# USB_OTG.net
KiCad netlist of a schematic drawn in Altium Designer
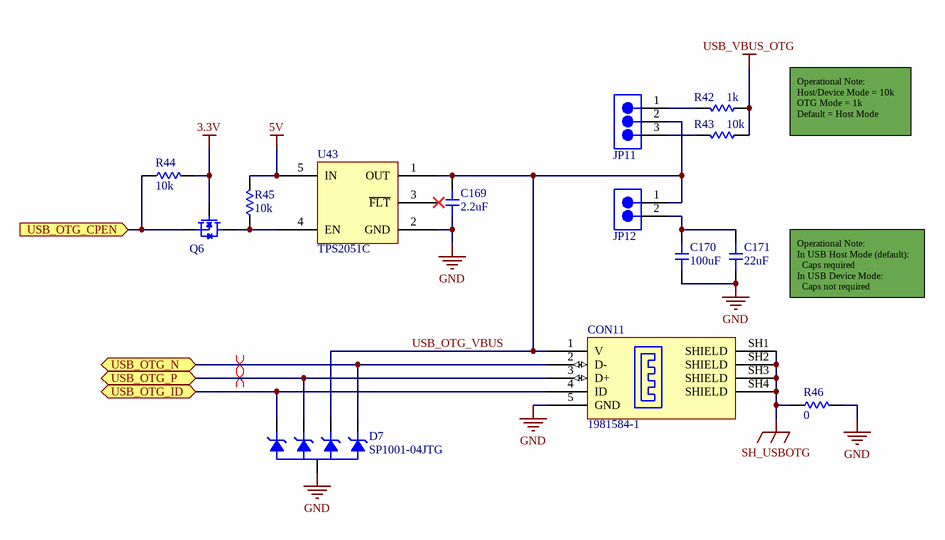
[diagram p0: USB_OTG.SchDoc]

(export (version "E")
  (design (tool "Eeschema 10.0.6"))
  (components
    (comp (ref "C169")
      (value "2.2uF")
      (footprint "0603-CAP")
      (description "Capacitor")
      (fields
        (field (name "MANUFACTURER") "Murata")
        (field (name "MANUFACTURER PART NUMBER") "GRM188R6YA225MA12D")
      )
      (libsource (lib "AMDC") (part "Capacitor"))
    )
    (comp (ref "C170")
      (value "100uF")
      (footprint "1812-CAP")
      (description "Capacitor")
      (fields
        (field (name "MANUFACTURER") "TDK")
        (field (name "MANUFACTURER PART NUMBER") "C4532X5R1A107M280KC")
      )
      (libsource (lib "AMDC") (part "Capacitor"))
    )
    (comp (ref "C171")
      (value "22uF")
      (footprint "0603-CAP")
      (description "Capacitor")
      (fields
        (field (name "MANUFACTURER") "Samsung")
        (field (name "MANUFACTURER PART NUMBER") "CL10A226MPCNUBE")
      )
      (libsource (lib "AMDC") (part "Capacitor"))
    )
    (comp (ref "CON11")
      (value "1981584-1")
      (footprint "1981584-1")
      (description "CONN RCPT MICRO USB TYPE AB")
      (fields (field (name "MANUFACTURER") "TE Connectivity"))
      (libsource (lib "AMDC") (part "1981584-1"))
    )
    (comp (ref "D7")
      (value "SP1001-04JTG")
      (footprint "SC70-5")
      (description "TVS DIODE 5.5V 13V SC70-5")
      (fields (field (name "MANUFACTURER") "Littelfuse"))
      (libsource (lib "AMDC") (part "SP1001-04JTG"))
    )
    (comp (ref "JP11")
      (value "Jumper3")
      (footprint "PIN_HEADER_1X3")
      (fields
        (field (name "MANUFACTURER") "Wurth Electronics")
        (field (name "MANUFACTURER PART NUMBER") "61300311121")
      )
      (libsource (lib "AMDC") (part "Jumper3"))
    )
    (comp (ref "JP12")
      (value "Jumper2")
      (footprint "PIN_HEADER_1x2")
      (fields
        (field (name "MANUFACTURER") "Wurth Electronics")
        (field (name "MANUFACTURER PART NUMBER") "61300211121")
      )
      (libsource (lib "AMDC") (part "Jumper2"))
    )
    (comp (ref "Q6")
      (value "MOSFET")
      (footprint "SOT95P250-3N")
      (fields (field (name "MANUFACTURER") "Diodes") (field (name "MANUFACTURER PART NUMBER") "DMN65D8L-7"))
      (libsource (lib "AMDC") (part "MOSFET"))
    )
    (comp (ref "R42")
      (value "1k")
      (footprint "0603-RES")
      (description "Resistor")
      (fields
        (field (name "MANUFACTURER") "Panasonic")
        (field (name "MANUFACTURER PART NUMBER") "ERJ-3EKF1001V")
      )
      (libsource (lib "AMDC") (part "Resistor"))
    )
    (comp (ref "R43")
      (value "10k")
      (footprint "0603-RES")
      (description "Resistor")
      (fields
        (field (name "MANUFACTURER") "Panasonic")
        (field (name "MANUFACTURER PART NUMBER") "ERJ-3EKF1002V")
      )
      (libsource (lib "AMDC") (part "Resistor"))
    )
    (comp (ref "R44")
      (value "10k")
      (footprint "0603-RES")
      (description "Resistor")
      (fields
        (field (name "MANUFACTURER") "Panasonic")
        (field (name "MANUFACTURER PART NUMBER") "ERJ-3EKF1002V")
      )
      (libsource (lib "AMDC") (part "Resistor"))
    )
    (comp (ref "R45")
      (value "10k")
      (footprint "0603-RES")
      (description "Resistor")
      (fields
        (field (name "MANUFACTURER") "Panasonic")
        (field (name "MANUFACTURER PART NUMBER") "ERJ-3EKF1002V")
      )
      (libsource (lib "AMDC") (part "Resistor"))
    )
    (comp (ref "R46")
      (value "0")
      (footprint "0603-RES")
      (description "Resistor")
      (fields
        (field (name "MANUFACTURER") "Panasonic")
        (field (name "MANUFACTURER PART NUMBER") "ERJ-3GEY0R00V")
      )
      (libsource (lib "AMDC") (part "Resistor"))
    )
    (comp (ref "U43")
      (value "TPS2051C")
      (footprint "SOT23-5")
      (description "IC USB PWR SW 1CH 0.5A SOT23-5")
      (fields
        (field (name "MANUFACTURER") "Texas Instruments")
        (field (name "MANUFACTURER PART NUMBER") "TPS2051CDBVT")
      )
      (libsource (lib "AMDC") (part "TPS2051C"))
    )
  )
  (nets
    (net (code "1") (name "/USB_OTG_CPEN") (class "Default")
      (node (ref "Q6") (pin "2") (pinfunction "S_2") (pintype "passive"))
      (node (ref "R44") (pin "1") (pinfunction "1_1") (pintype "passive"))
    )
    (net (code "2") (name "/USB_OTG_ID") (class "Default")
      (node (ref "CON11") (pin "4") (pinfunction "ID_4") (pintype "passive"))
      (node (ref "D7") (pin "1") (pinfunction "C1_1") (pintype "passive"))
    )
    (net (code "3") (name "/USB_OTG_N") (class "Default")
      (node (ref "CON11") (pin "2") (pinfunction "D-_2") (pintype "bidirectional"))
      (node (ref "D7") (pin "4") (pinfunction "C4_4") (pintype "passive"))
    )
    (net (code "4") (name "/USB_OTG_P") (class "Default")
      (node (ref "CON11") (pin "3") (pinfunction "D+_3") (pintype "bidirectional"))
      (node (ref "D7") (pin "5") (pinfunction "C2_5") (pintype "passive"))
    )
    (net (code "5") (name "/USB_OTG_VBUS") (class "Default")
      (node (ref "C169") (pin "2") (pinfunction "2_2") (pintype "passive"))
      (node (ref "CON11") (pin "1") (pinfunction "V_1") (pintype "passive"))
      (node (ref "D7") (pin "3") (pinfunction "C3_3") (pintype "passive"))
      (node (ref "JP11") (pin "2") (pinfunction "75_2") (pintype "passive"))
      (node (ref "JP12") (pin "1") (pinfunction "76_1") (pintype "passive"))
      (node (ref "U43") (pin "1") (pinfunction "OUT_1") (pintype "passive"))
    )
    (net (code "6") (name "3.3V") (class "Default")
      (node (ref "Q6") (pin "1") (pinfunction "G_1") (pintype "passive"))
      (node (ref "R44") (pin "2") (pinfunction "2_2") (pintype "passive"))
    )
    (net (code "7") (name "5V") (class "Default")
      (node (ref "R45") (pin "2") (pinfunction "2_2") (pintype "passive"))
      (node (ref "U43") (pin "5") (pinfunction "IN_5") (pintype "passive"))
    )
    (net (code "8") (name "GND") (class "Default")
      (node (ref "C169") (pin "1") (pinfunction "1_1") (pintype "passive"))
      (node (ref "C170") (pin "1") (pinfunction "1_1") (pintype "passive"))
      (node (ref "C171") (pin "1") (pinfunction "1_1") (pintype "passive"))
      (node (ref "CON11") (pin "5") (pinfunction "GND_5") (pintype "passive"))
      (node (ref "D7") (pin "2") (pinfunction "A_2") (pintype "passive"))
      (node (ref "R46") (pin "2") (pinfunction "2_2") (pintype "passive"))
      (node (ref "U43") (pin "2") (pinfunction "GND_2") (pintype "passive"))
    )
    (net (code "9") (name "Net-(JP11-75-Pad3)") (class "Default")
      (node (ref "JP11") (pin "3") (pinfunction "75_3") (pintype "passive"))
      (node (ref "R43") (pin "2") (pinfunction "2_2") (pintype "passive"))
    )
    (net (code "10") (name "Net-(JP11-76)") (class "Default")
      (node (ref "JP11") (pin "1") (pinfunction "76_1") (pintype "passive"))
      (node (ref "R42") (pin "2") (pinfunction "2_2") (pintype "passive"))
    )
    (net (code "11") (name "Net-(JP12-75)") (class "Default")
      (node (ref "C170") (pin "2") (pinfunction "2_2") (pintype "passive"))
      (node (ref "C171") (pin "2") (pinfunction "2_2") (pintype "passive"))
      (node (ref "JP12") (pin "2") (pinfunction "75_2") (pintype "passive"))
    )
    (net (code "12") (name "Net-(Q6-D)") (class "Default")
      (node (ref "Q6") (pin "3") (pinfunction "D_3") (pintype "passive"))
      (node (ref "R45") (pin "1") (pinfunction "1_1") (pintype "passive"))
      (node (ref "U43") (pin "4") (pinfunction "EN_4") (pintype "passive"))
    )
    (net (code "13") (name "SH_USBOTG") (class "Default")
      (node (ref "CON11") (pin "SH1") (pinfunction "SHIELD_SH1") (pintype "passive"))
      (node (ref "CON11") (pin "SH2") (pinfunction "SHIELD_SH2") (pintype "passive"))
      (node (ref "CON11") (pin "SH3") (pinfunction "SHIELD_SH3") (pintype "passive"))
      (node (ref "CON11") (pin "SH4") (pinfunction "SHIELD_SH4") (pintype "passive"))
      (node (ref "R46") (pin "1") (pinfunction "1_1") (pintype "passive"))
    )
    (net (code "14") (name "USB_VBUS_OTG") (class "Default")
      (node (ref "R42") (pin "1") (pinfunction "1_1") (pintype "passive"))
      (node (ref "R43") (pin "1") (pinfunction "1_1") (pintype "passive"))
    )
    (net (code "15") (name "unconnected-(U43-~{FLT}-Pad3)") (class "Default")
      (node (ref "U43") (pin "3") (pinfunction "~{FLT}_3") (pintype "passive+no_connect"))
    )
  )
)
